# LEO_COTS_amps_tripler_rev1.net
KiCad netlist of a schematic drawn in Altium Designer
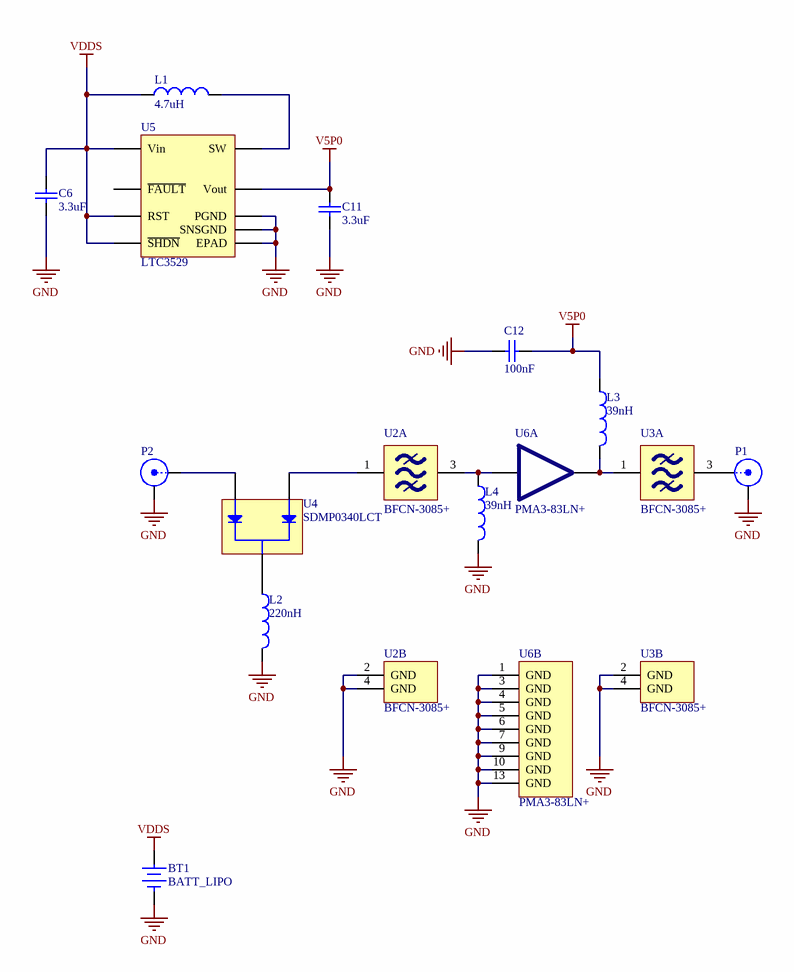
[diagram p0: LEO_COTS_amps_tripler_rev1.SchDoc]

(export (version "E")
  (design (tool "Eeschema 10.0.6"))
  (components
    (comp (ref "BT1")
      (value "BATT_LIPO")
      (footprint "LIPO_1cm_1cm")
      (libsource (lib "LEO_COTS_components") (part "BATT_LIPO"))
    )
    (comp (ref "C6")
      (value "3.3uF")
      (footprint "CAPC1608X05N")
      (description "CAP CER 3.3uF 0603")
      (fields (field (name "Comment") "CAP_0603"))
      (libsource (lib "LEO_COTS_components") (part "CAP_0603"))
    )
    (comp (ref "C11")
      (value "3.3uF")
      (footprint "CAPC1608X05N")
      (description "CAP CER 3.3uF 0603")
      (fields (field (name "Comment") "CAP_0603"))
      (libsource (lib "LEO_COTS_components") (part "CAP_0603"))
    )
    (comp (ref "C12")
      (value "100nF")
      (footprint "CAPC0603X04N")
      (description "CAP CER 100nF 0201")
      (fields (field (name "Comment") "CAP_0201"))
      (libsource (lib "LEO_COTS_components") (part "CAP_0201"))
    )
    (comp (ref "L1")
      (value "4.7uH")
      (footprint "C0805")
      (description "Inductor")
      (fields (field (name "PUBLISHER") "Altium Limited"))
      (libsource (lib "LEO_COTS_components") (part "Inductor"))
    )
    (comp (ref "L2")
      (value "220nH")
      (footprint "0402")
      (description "Inductor")
      (fields (field (name "PUBLISHER") "Altium Limited"))
      (libsource (lib "LEO_COTS_components") (part "Inductor"))
    )
    (comp (ref "L3")
      (value "39nH")
      (footprint "0402")
      (description "Inductor")
      (fields (field (name "PUBLISHER") "Altium Limited"))
      (libsource (lib "LEO_COTS_components") (part "Inductor"))
    )
    (comp (ref "L4")
      (value "39nH")
      (footprint "0402")
      (description "Inductor")
      (fields (field (name "PUBLISHER") "Altium Limited"))
      (libsource (lib "LEO_COTS_components") (part "Inductor"))
    )
    (comp (ref "P1")
      (value "1909763-1")
      (footprint "1909763-1")
      (description "CONN UMCC JACK STR 50OHM SMD")
      (libsource (lib "LEO_COTS_components") (part "1909763-1"))
    )
    (comp (ref "P2")
      (value "1909763-1")
      (footprint "1909763-1")
      (description "CONN UMCC JACK STR 50OHM SMD")
      (libsource (lib "LEO_COTS_components") (part "1909763-1"))
    )
    (comp (ref "U2")
      (value "BFCN-3085+")
      (footprint "FV1206")
      (description "2800 to 3400 MHz Band-Pass Filter")
      (libsource (lib "LEO_COTS_components") (part "BFCN-3085+"))
    )
    (comp (ref "U3")
      (value "BFCN-3085+")
      (footprint "FV1206")
      (description "2800 to 3400 MHz Band-Pass Filter")
      (libsource (lib "LEO_COTS_components") (part "BFCN-3085+"))
    )
    (comp (ref "U4")
      (value "SDMP0340LCT")
      (footprint "SOT-523")
      (description "Dual Common Cathode Schottky")
      (libsource (lib "LEO_COTS_components") (part "SDMP0340LCT"))
    )
    (comp (ref "U5")
      (value "LTC3529")
      (footprint "8-DFN")
      (description "5V Boost Converter")
      (libsource (lib "LEO_COTS_components") (part "LTC3529"))
    )
    (comp (ref "U6")
      (value "PMA3-83LN+")
      (footprint "DQ1225")
      (description "Wideband LNA")
      (libsource (lib "LEO_COTS_components") (part "PMA3-83LN+"))
    )
  )
  (nets
    (net (code "1") (name "GND") (class "Default")
      (node (ref "BT1") (pin "2") (pinfunction "-_2") (pintype "passive"))
      (node (ref "C11") (pin "1") (pinfunction "1_1") (pintype "passive"))
      (node (ref "C12") (pin "1") (pinfunction "1_1") (pintype "passive"))
      (node (ref "C6") (pin "1") (pinfunction "1_1") (pintype "passive"))
      (node (ref "L2") (pin "2") (pinfunction "2_2") (pintype "passive"))
      (node (ref "L4") (pin "2") (pinfunction "2_2") (pintype "passive"))
      (node (ref "P1") (pin "2") (pinfunction "Y_2") (pintype "passive"))
      (node (ref "P2") (pin "2") (pinfunction "Y_2") (pintype "passive"))
      (node (ref "U2") (pin "2") (pinfunction "GND_2") (pintype "tri_state"))
      (node (ref "U2") (pin "4") (pinfunction "GND_4") (pintype "tri_state"))
      (node (ref "U3") (pin "2") (pinfunction "GND_2") (pintype "tri_state"))
      (node (ref "U3") (pin "4") (pinfunction "GND_4") (pintype "tri_state"))
      (node (ref "U5") (pin "4") (pinfunction "PGND_4") (pintype "passive"))
      (node (ref "U5") (pin "6") (pinfunction "SNSGND_6") (pintype "passive"))
      (node (ref "U5") (pin "9") (pinfunction "EPAD_9") (pintype "passive"))
      (node (ref "U6") (pin "1") (pinfunction "GND_1") (pintype "tri_state"))
      (node (ref "U6") (pin "10") (pinfunction "GND_10") (pintype "tri_state"))
      (node (ref "U6") (pin "13") (pinfunction "GND_13") (pintype "tri_state"))
      (node (ref "U6") (pin "3") (pinfunction "GND_3") (pintype "tri_state"))
      (node (ref "U6") (pin "4") (pinfunction "GND_4") (pintype "tri_state"))
      (node (ref "U6") (pin "5") (pinfunction "GND_5") (pintype "tri_state"))
      (node (ref "U6") (pin "6") (pinfunction "GND_6") (pintype "tri_state"))
      (node (ref "U6") (pin "7") (pinfunction "GND_7") (pintype "tri_state"))
      (node (ref "U6") (pin "9") (pinfunction "GND_9") (pintype "tri_state"))
    )
    (net (code "2") (name "Net-(L2-Pad1)") (class "Default")
      (node (ref "L2") (pin "1") (pinfunction "1_1") (pintype "passive"))
      (node (ref "U4") (pin "3") (pinfunction "3_3") (pintype "passive"))
    )
    (net (code "3") (name "Net-(P1-X)") (class "Default")
      (node (ref "P1") (pin "1") (pinfunction "X_1") (pintype "passive"))
      (node (ref "U3") (pin "3") (pinfunction "OUT_3") (pintype "tri_state"))
    )
    (net (code "4") (name "Net-(P2-X)") (class "Default")
      (node (ref "P2") (pin "1") (pinfunction "X_1") (pintype "passive"))
      (node (ref "U4") (pin "1") (pinfunction "1_1") (pintype "passive"))
    )
    (net (code "5") (name "Net-(U2A-IN)") (class "Default")
      (node (ref "U2") (pin "1") (pinfunction "IN_1") (pintype "tri_state"))
      (node (ref "U4") (pin "2") (pinfunction "2_2") (pintype "passive"))
    )
    (net (code "6") (name "Net-(U2A-OUT)") (class "Default")
      (node (ref "L4") (pin "1") (pinfunction "1_1") (pintype "passive"))
      (node (ref "U2") (pin "3") (pinfunction "OUT_3") (pintype "tri_state"))
      (node (ref "U6") (pin "2") (pinfunction "IN_2") (pintype "tri_state"))
    )
    (net (code "7") (name "Net-(U3A-IN)") (class "Default")
      (node (ref "L3") (pin "2") (pinfunction "2_2") (pintype "passive"))
      (node (ref "U3") (pin "1") (pinfunction "IN_1") (pintype "tri_state"))
      (node (ref "U6") (pin "8") (pinfunction "OUT_8") (pintype "tri_state"))
    )
    (net (code "8") (name "Net-(U5-SW)") (class "Default")
      (node (ref "L1") (pin "2") (pinfunction "2_2") (pintype "passive"))
      (node (ref "U5") (pin "2") (pinfunction "SW_2") (pintype "passive"))
    )
    (net (code "9") (name "V5P0") (class "Default")
      (node (ref "C11") (pin "2") (pinfunction "2_2") (pintype "passive"))
      (node (ref "C12") (pin "2") (pinfunction "2_2") (pintype "passive"))
      (node (ref "L3") (pin "1") (pinfunction "1_1") (pintype "passive"))
      (node (ref "U5") (pin "1") (pinfunction "Vout_1") (pintype "passive"))
    )
    (net (code "10") (name "VDDS") (class "Default")
      (node (ref "BT1") (pin "1") (pinfunction "+_1") (pintype "passive"))
      (node (ref "C6") (pin "2") (pinfunction "2_2") (pintype "passive"))
      (node (ref "L1") (pin "1") (pinfunction "1_1") (pintype "passive"))
      (node (ref "U5") (pin "3") (pinfunction "~{SHDN}_3") (pintype "passive"))
      (node (ref "U5") (pin "7") (pinfunction "RST_7") (pintype "passive"))
      (node (ref "U5") (pin "8") (pinfunction "Vin_8") (pintype "passive"))
    )
    (net (code "11") (name "unconnected-(U5-~{FAULT}-Pad5)") (class "Default")
      (node (ref "U5") (pin "5") (pinfunction "~{FAULT}_5") (pintype "passive"))
    )
  )
)
